# PdlSerialAdapter.net
KiCad netlist of a schematic drawn in EAGLE
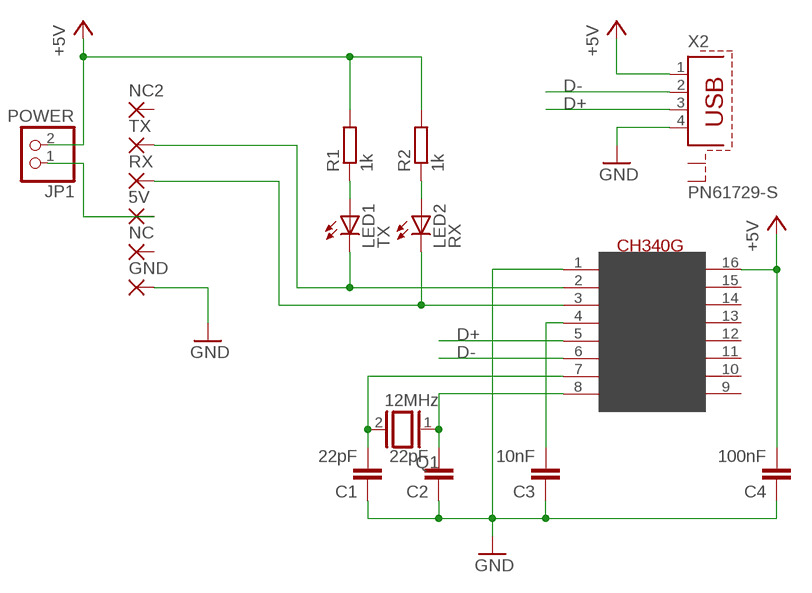
[diagram p0: schematic, sheet 1]

(export (version "E")
  (design (tool "Eeschema 10.0.6"))
  (components
    (comp (ref "5V")
      (value "SMD2")
      (footprint "eagle-import:SMD1,27-2,54")
      (libsource (lib "eagle-import") (part "SMD2"))
    )
    (comp (ref "C1")
      (value "22pF")
      (footprint "eagle-import:C025-025X050")
      (libsource (lib "eagle-import") (part "C-EU025-025X050"))
    )
    (comp (ref "C2")
      (value "22pF")
      (footprint "eagle-import:C025-025X050")
      (libsource (lib "eagle-import") (part "C-EU025-025X050"))
    )
    (comp (ref "C3")
      (value "10nF")
      (footprint "eagle-import:C050-030X075")
      (libsource (lib "eagle-import") (part "C-EU050-030X075"))
    )
    (comp (ref "C4")
      (value "100nF")
      (footprint "eagle-import:C050-030X075")
      (libsource (lib "eagle-import") (part "C-EU050-030X075"))
    )
    (comp (ref "GND")
      (value "SMD2")
      (footprint "eagle-import:SMD1,27-2,54")
      (libsource (lib "eagle-import") (part "SMD2"))
    )
    (comp (ref "JP1")
      (value "POWER")
      (footprint "eagle-import:1X02")
      (libsource (lib "eagle-import") (part "PINHD-1X2"))
    )
    (comp (ref "LED1")
      (value "TX")
      (footprint "eagle-import:LED3MM")
      (libsource (lib "eagle-import") (part "LED3MM"))
    )
    (comp (ref "LED2")
      (value "RX")
      (footprint "eagle-import:LED3MM")
      (libsource (lib "eagle-import") (part "LED3MM"))
    )
    (comp (ref "NC")
      (value "SMD2")
      (footprint "eagle-import:SMD1,27-2,54")
      (libsource (lib "eagle-import") (part "SMD2"))
    )
    (comp (ref "NC2")
      (value "SMD2")
      (footprint "eagle-import:SMD1,27-2,54")
      (libsource (lib "eagle-import") (part "SMD2"))
    )
    (comp (ref "Q1")
      (value "12MHz")
      (footprint "eagle-import:QS")
      (libsource (lib "eagle-import") (part "XTAL/S"))
    )
    (comp (ref "R1")
      (value "1k")
      (footprint "eagle-import:0207_2V")
      (libsource (lib "eagle-import") (part "R-EU_0207/2V"))
    )
    (comp (ref "R2")
      (value "1k")
      (footprint "eagle-import:0207_2V")
      (libsource (lib "eagle-import") (part "R-EU_0207/2V"))
    )
    (comp (ref "RX")
      (value "SMD2")
      (footprint "eagle-import:SMD1,27-2,54")
      (libsource (lib "eagle-import") (part "SMD2"))
    )
    (comp (ref "TX")
      (value "SMD2")
      (footprint "eagle-import:SMD1,27-2,54")
      (libsource (lib "eagle-import") (part "SMD2"))
    )
    (comp (ref "U$1")
      (value "CH340G")
      (footprint "eagle-import:SOIC16")
      (libsource (lib "eagle-import") (part "CH340G"))
    )
    (comp (ref "X2")
      (value "PN61729-S")
      (footprint "eagle-import:PN61729-S")
      (libsource (lib "eagle-import") (part "PN61729-S"))
    )
  )
  (nets
    (net (code "1") (name "+5V") (class "Default")
      (node (ref "C4") (pin "2") (pinfunction "2_2") (pintype "passive"))
      (node (ref "JP1") (pin "2") (pinfunction "2_2") (pintype "passive"))
      (node (ref "R1") (pin "2") (pinfunction "2_2") (pintype "passive"))
      (node (ref "R2") (pin "2") (pinfunction "2_2") (pintype "passive"))
      (node (ref "U$1") (pin "16") (pinfunction "VCC_16") (pintype "bidirectional"))
      (node (ref "X2") (pin "1") (pinfunction "1_1") (pintype "passive"))
    )
    (net (code "2") (name "/D+") (class "Default")
      (node (ref "U$1") (pin "5") (pinfunction "D+_5") (pintype "bidirectional"))
      (node (ref "X2") (pin "3") (pinfunction "3_3") (pintype "passive"))
    )
    (net (code "3") (name "/D-") (class "Default")
      (node (ref "U$1") (pin "6") (pinfunction "D-_6") (pintype "bidirectional"))
      (node (ref "X2") (pin "2") (pinfunction "2_2") (pintype "passive"))
    )
    (net (code "4") (name "GND") (class "Default")
      (node (ref "C1") (pin "1") (pinfunction "1_1") (pintype "passive"))
      (node (ref "C2") (pin "1") (pinfunction "1_1") (pintype "passive"))
      (node (ref "C3") (pin "1") (pinfunction "1_1") (pintype "passive"))
      (node (ref "C4") (pin "1") (pinfunction "1_1") (pintype "passive"))
      (node (ref "GND") (pin "1") (pinfunction "P_1") (pintype "passive"))
      (node (ref "U$1") (pin "1") (pinfunction "GND_1") (pintype "bidirectional"))
      (node (ref "X2") (pin "4") (pinfunction "4_4") (pintype "passive"))
    )
    (net (code "5") (name "Net-(5V-P)") (class "Default")
      (node (ref "5V") (pin "1") (pinfunction "P_1") (pintype "passive"))
      (node (ref "JP1") (pin "1") (pinfunction "1_1") (pintype "passive"))
    )
    (net (code "6") (name "Net-(LED1-C)") (class "Default")
      (node (ref "LED1") (pin "K") (pinfunction "C_K") (pintype "passive"))
      (node (ref "TX") (pin "1") (pinfunction "P_1") (pintype "passive"))
      (node (ref "U$1") (pin "2") (pinfunction "TX_2") (pintype "bidirectional"))
    )
    (net (code "7") (name "Net-(LED1-PadA)") (class "Default")
      (node (ref "LED1") (pin "A") (pinfunction "A_A") (pintype "passive"))
      (node (ref "R1") (pin "1") (pinfunction "1_1") (pintype "passive"))
    )
    (net (code "8") (name "Net-(LED2-C)") (class "Default")
      (node (ref "LED2") (pin "K") (pinfunction "C_K") (pintype "passive"))
      (node (ref "RX") (pin "1") (pinfunction "P_1") (pintype "passive"))
      (node (ref "U$1") (pin "3") (pinfunction "RX_3") (pintype "bidirectional"))
    )
    (net (code "9") (name "Net-(LED2-PadA)") (class "Default")
      (node (ref "LED2") (pin "A") (pinfunction "A_A") (pintype "passive"))
      (node (ref "R2") (pin "1") (pinfunction "1_1") (pintype "passive"))
    )
    (net (code "10") (name "Net-(U$1-V3)") (class "Default")
      (node (ref "C3") (pin "2") (pinfunction "2_2") (pintype "passive"))
      (node (ref "U$1") (pin "4") (pinfunction "V3_4") (pintype "bidirectional"))
    )
    (net (code "11") (name "Net-(U$1-XI)") (class "Default")
      (node (ref "C1") (pin "2") (pinfunction "2_2") (pintype "passive"))
      (node (ref "Q1") (pin "2") (pinfunction "2_2") (pintype "passive"))
      (node (ref "U$1") (pin "7") (pinfunction "XI_7") (pintype "bidirectional"))
    )
    (net (code "12") (name "Net-(U$1-XO)") (class "Default")
      (node (ref "C2") (pin "2") (pinfunction "2_2") (pintype "passive"))
      (node (ref "Q1") (pin "1") (pinfunction "1_1") (pintype "passive"))
      (node (ref "U$1") (pin "8") (pinfunction "XO_8") (pintype "bidirectional"))
    )
    (net (code "13") (name "unconnected-(NC-P-Pad1)") (class "Default")
      (node (ref "NC") (pin "1") (pinfunction "P_1") (pintype "passive"))
    )
    (net (code "14") (name "unconnected-(NC2-P-Pad1)") (class "Default")
      (node (ref "NC2") (pin "1") (pinfunction "P_1") (pintype "passive"))
    )
    (net (code "15") (name "unconnected-(U$1-CTS-Pad9)") (class "Default")
      (node (ref "U$1") (pin "9") (pinfunction "CTS_9") (pintype "bidirectional"))
    )
    (net (code "16") (name "unconnected-(U$1-DCD-Pad12)") (class "Default")
      (node (ref "U$1") (pin "12") (pinfunction "DCD_12") (pintype "bidirectional"))
    )
    (net (code "17") (name "unconnected-(U$1-DSR-Pad10)") (class "Default")
      (node (ref "U$1") (pin "10") (pinfunction "DSR_10") (pintype "bidirectional"))
    )
    (net (code "18") (name "unconnected-(U$1-DTR-Pad13)") (class "Default")
      (node (ref "U$1") (pin "13") (pinfunction "DTR_13") (pintype "bidirectional"))
    )
    (net (code "19") (name "unconnected-(U$1-RI-Pad11)") (class "Default")
      (node (ref "U$1") (pin "11") (pinfunction "RI_11") (pintype "bidirectional"))
    )
    (net (code "20") (name "unconnected-(U$1-RS232-Pad15)") (class "Default")
      (node (ref "U$1") (pin "15") (pinfunction "RS232_15") (pintype "bidirectional"))
    )
    (net (code "21") (name "unconnected-(U$1-RTS-Pad14)") (class "Default")
      (node (ref "U$1") (pin "14") (pinfunction "RTS_14") (pintype "bidirectional"))
    )
    (net (code "22") (name "unconnected-(X2-PadS1)") (class "Default")
      (node (ref "X2") (pin "S1") (pinfunction "S1_S1") (pintype "passive"))
    )
    (net (code "23") (name "unconnected-(X2-PadS2)") (class "Default")
      (node (ref "X2") (pin "S2") (pinfunction "S2_S2") (pintype "passive"))
    )
  )
)
